# Companion_bot_schematic.net
KiCad netlist of a schematic drawn in EAGLE
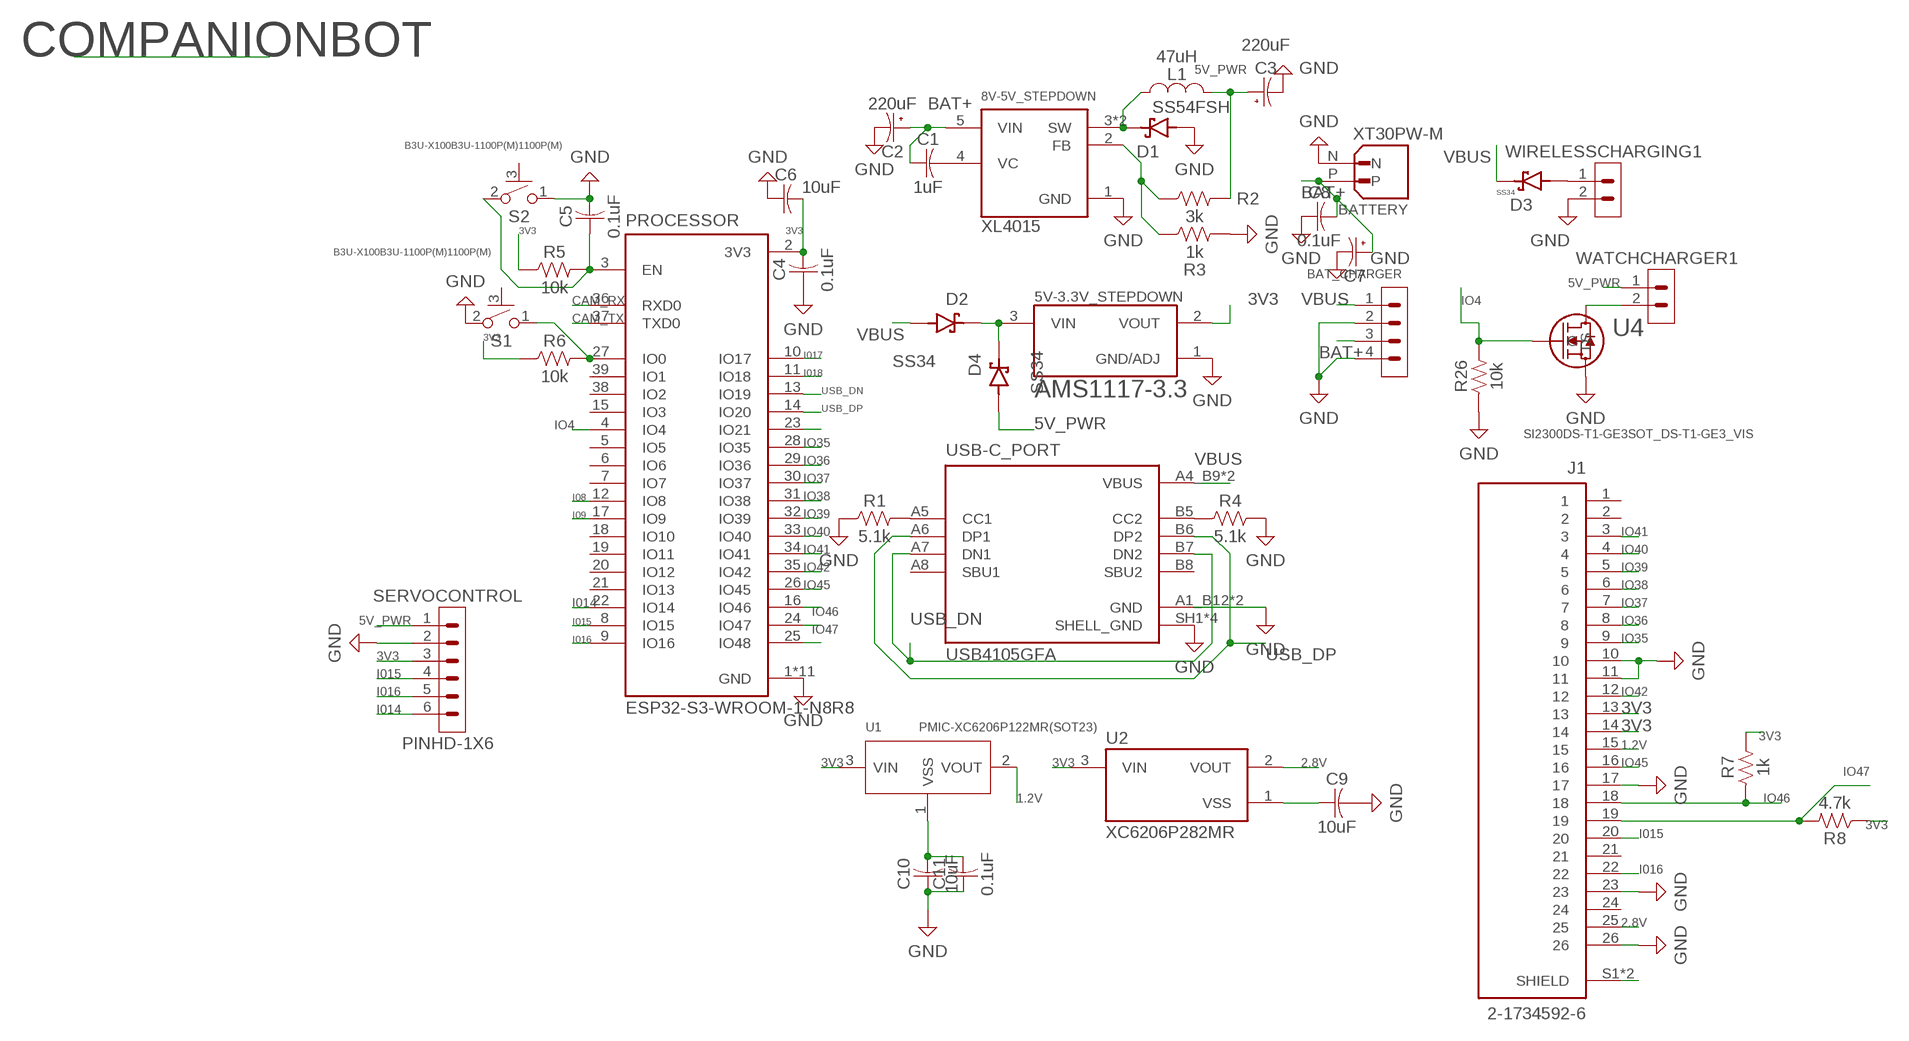
[diagram p0: schematic, sheet 1]

(export (version "E")
  (design (tool "Eeschema 10.0.6"))
  (components
    (comp (ref "5V-3.3V_STEPDOWN")
      (value "AMS1117-3.3")
      (footprint "eagle-import:SOT229P700X180-4N")
      (fields (field (name "MF") "Advanced Monolithic Systems"))
      (libsource (lib "eagle-import") (part "AMS1117-3.3"))
    )
    (comp (ref "8V-5V_STEPDOWN")
      (value "XL4015")
      (footprint "eagle-import:CONV_XL4015")
      (fields (field (name "MF") "XLSEMI"))
      (libsource (lib "eagle-import") (part "XL4015"))
    )
    (comp (ref "BATTERY")
      (value "XT30PW-M")
      (footprint "eagle-import:AMASS_XT30PW-M")
      (fields (field (name "MF") "AMASS"))
      (libsource (lib "eagle-import") (part "XT30PW-M"))
    )
    (comp (ref "BAT_CHARGER")
      (value "PINHD-1X4")
      (footprint "eagle-import:1X04")
      (libsource (lib "eagle-import") (part "PINHD-1X4"))
    )
    (comp (ref "C1")
      (value "1uF")
      (footprint "eagle-import:CAPC1005X60")
      (libsource (lib "eagle-import") (part "C-USCHIP-0402(1005-METRIC)_"))
    )
    (comp (ref "C2")
      (value "220uF")
      (footprint "eagle-import:CAPMP3216X180N")
      (libsource (lib "eagle-import") (part "C-POL-USTANTALUM-1206(3216-METRIC)_"))
    )
    (comp (ref "C3")
      (value "220uF")
      (footprint "eagle-import:CAPMP3216X180N")
      (libsource (lib "eagle-import") (part "C-POL-USTANTALUM-1206(3216-METRIC)_"))
    )
    (comp (ref "C4")
      (value "0.1uF")
      (footprint "eagle-import:CAPC1005X60")
      (libsource (lib "eagle-import") (part "C-USCHIP-0402(1005-METRIC)_"))
    )
    (comp (ref "C5")
      (value "0.1uF")
      (footprint "eagle-import:CAPC1005X60")
      (libsource (lib "eagle-import") (part "C-USCHIP-0402(1005-METRIC)_"))
    )
    (comp (ref "C6")
      (value "10uF")
      (footprint "eagle-import:CAPC1005X60")
      (libsource (lib "eagle-import") (part "C-USCHIP-0402(1005-METRIC)_"))
    )
    (comp (ref "C7")
      (value "C-POL-US_TANTALUM-1206(3216-METRIC)")
      (footprint "eagle-import:CAPMP3216X180N")
      (libsource (lib "eagle-import") (part "C-POL-USTANTALUM-1206(3216-METRIC)_"))
    )
    (comp (ref "C8")
      (value "0.1uF")
      (footprint "eagle-import:CAPC1005X60")
      (libsource (lib "eagle-import") (part "C-USCHIP-0402(1005-METRIC)_"))
    )
    (comp (ref "C9")
      (value "10uF")
      (footprint "eagle-import:CAPC1005X60")
      (libsource (lib "eagle-import") (part "C-USCHIP-0402(1005-METRIC)_"))
    )
    (comp (ref "C10")
      (value "10uF")
      (footprint "eagle-import:CAPC1005X60")
      (libsource (lib "eagle-import") (part "C-USCHIP-0402(1005-METRIC)_"))
    )
    (comp (ref "C11")
      (value "0.1uF")
      (footprint "eagle-import:CAPC1005X60")
      (libsource (lib "eagle-import") (part "C-USCHIP-0402(1005-METRIC)_"))
    )
    (comp (ref "D1")
      (value "SS54FSH")
      (footprint "eagle-import:SODFL4725X110N")
      (fields (field (name "MF") "Taiwan Semiconductor"))
      (libsource (lib "eagle-import") (part "SS54FSH"))
    )
    (comp (ref "D2")
      (value "SS34")
      (footprint "eagle-import:DIO_SS34")
      (fields (field (name "MF") "Taiwan Semiconductor"))
      (libsource (lib "eagle-import") (part "SS34"))
    )
    (comp (ref "D3")
      (value "SS34")
      (footprint "eagle-import:DIO_SS34")
      (fields (field (name "MF") "Taiwan Semiconductor"))
      (libsource (lib "eagle-import") (part "SS34"))
    )
    (comp (ref "D4")
      (value "SS34")
      (footprint "eagle-import:DIO_SS34")
      (fields (field (name "MF") "Taiwan Semiconductor"))
      (libsource (lib "eagle-import") (part "SS34"))
    )
    (comp (ref "J1")
      (value "2-1734592-6")
      (footprint "eagle-import:TE_2-1734592-6")
      (fields (field (name "MF") "TE Connectivity"))
      (libsource (lib "eagle-import") (part "2-1734592-6"))
    )
    (comp (ref "L1")
      (value "47uH")
      (footprint "eagle-import:INDC1006X60N")
      (libsource (lib "eagle-import") (part "LCHIP-0402(1006-METRIC)_"))
    )
    (comp (ref "PROCESSOR")
      (value "ESP32-S3-WROOM-1-N8R8")
      (footprint "eagle-import:XCVR_ESP32S3WROOM1N8R8")
      (fields (field (name "MF") "Espressif Systems"))
      (libsource (lib "eagle-import") (part "ESP32-S3-WROOM-1-N8R8"))
    )
    (comp (ref "R1")
      (value "5.1k")
      (footprint "eagle-import:RESC1005X40")
      (libsource (lib "eagle-import") (part "R-USCHIP-0402(1005-METRIC)_"))
    )
    (comp (ref "R2")
      (value "3k")
      (footprint "eagle-import:RESC1005X40")
      (libsource (lib "eagle-import") (part "R-USCHIP-0402(1005-METRIC)_"))
    )
    (comp (ref "R3")
      (value "1k")
      (footprint "eagle-import:RESC1005X40")
      (libsource (lib "eagle-import") (part "R-USCHIP-0402(1005-METRIC)_"))
    )
    (comp (ref "R4")
      (value "5.1k")
      (footprint "eagle-import:RESC1005X40")
      (libsource (lib "eagle-import") (part "R-USCHIP-0402(1005-METRIC)_"))
    )
    (comp (ref "R5")
      (value "10k")
      (footprint "eagle-import:RESC1005X40")
      (libsource (lib "eagle-import") (part "R-USCHIP-0402(1005-METRIC)_"))
    )
    (comp (ref "R6")
      (value "10k")
      (footprint "eagle-import:RESC1005X40")
      (libsource (lib "eagle-import") (part "R-USCHIP-0402(1005-METRIC)_"))
    )
    (comp (ref "R7")
      (value "1k")
      (footprint "eagle-import:RESC1005X40")
      (libsource (lib "eagle-import") (part "R-USCHIP-0402(1005-METRIC)_"))
    )
    (comp (ref "R8")
      (value "4.7k")
      (footprint "eagle-import:RESC1005X40")
      (libsource (lib "eagle-import") (part "R-USCHIP-0402(1005-METRIC)_"))
    )
    (comp (ref "R26")
      (value "10k")
      (footprint "eagle-import:RESC1005X40")
      (libsource (lib "eagle-import") (part "R-USCHIP-0402(1005-METRIC)_"))
    )
    (comp (ref "S1")
      (value "B3U-X100B3U-1100P(M)1100P(M)")
      (footprint "eagle-import:B3U-1100P(M)")
      (fields (field (name "MANUFACTURER") "Omron Electronics Inc-EMC Div") (field (name "MPN") "B3U-1100PM"))
      (libsource (lib "eagle-import") (part "B3U-X1001100P(M)B3U-1100P(M)"))
    )
    (comp (ref "S2")
      (value "B3U-X100B3U-1100P(M)1100P(M)")
      (footprint "eagle-import:B3U-1100P(M)")
      (fields (field (name "MANUFACTURER") "Omron Electronics Inc-EMC Div") (field (name "MPN") "B3U-1100PM"))
      (libsource (lib "eagle-import") (part "B3U-X1001100P(M)B3U-1100P(M)"))
    )
    (comp (ref "SERVOCONTROL")
      (value "PINHD-1X6")
      (footprint "eagle-import:1X06")
      (libsource (lib "eagle-import") (part "PINHD-1X6"))
    )
    (comp (ref "U1")
      (value "PMIC-XC6206P122MR(SOT23)")
      (footprint "eagle-import:SOT-23")
      (fields (field (name "MF") "Torex") (field (name "MP") "XC6206P122MR"))
      (libsource (lib "eagle-import") (part "PMIC-XC6206P122MR(SOT23)"))
    )
    (comp (ref "U2")
      (value "XC6206P282MR")
      (footprint "eagle-import:VREG_XC6206P282MR")
      (fields (field (name "MF") "Torex Semiconductor Ltd"))
      (libsource (lib "eagle-import") (part "XC6206P282MR"))
    )
    (comp (ref "U4")
      (value "SI2300DS-T1-GE3SOT_DS-T1-GE3_VIS")
      (footprint "eagle-import:SOT_DS-T1-GE3_VIS")
      (fields
        (field (name "MANUFACTURER_PART_NUMBER") "SI2300DS-T1-GE3")
        (field (name "COPYRIGHT") "Copyright (C) 2026 Ultra Librarian. All rights reserved.")
      )
      (libsource (lib "eagle-import") (part "SI2300DS-T1-GE3SOT_DS-T1-GE3_VIS"))
    )
    (comp (ref "USB-C_PORT")
      (value "USB4105GFA")
      (footprint "eagle-import:GCT_USB4105GFA")
      (fields (field (name "MF") "Global Connector Technology"))
      (libsource (lib "eagle-import") (part "USB4105GFA"))
    )
    (comp (ref "WATCHCHARGER1")
      (value "PINHD-1X2")
      (footprint "eagle-import:1X02")
      (libsource (lib "eagle-import") (part "PINHD-1X2"))
    )
    (comp (ref "WIRELESSCHARGING1")
      (value "PINHD-1X2")
      (footprint "eagle-import:1X02")
      (libsource (lib "eagle-import") (part "PINHD-1X2"))
    )
  )
  (nets
    (net (code "1") (name "/1.2V") (class "Default")
      (node (ref "J1") (pin "15") (pinfunction "15_15") (pintype "passive"))
      (node (ref "U1") (pin "2") (pinfunction "VOUT_2") (pintype "output"))
    )
    (net (code "2") (name "/2.8V") (class "Default")
      (node (ref "J1") (pin "25") (pinfunction "25_25") (pintype "passive"))
      (node (ref "U2") (pin "2") (pinfunction "VOUT_2") (pintype "output"))
    )
    (net (code "3") (name "/3V3") (class "Default")
      (node (ref "5V-3.3V_STEPDOWN") (pin "2") (pinfunction "VOUT_2") (pintype "output"))
      (node (ref "C4") (pin "2") (pinfunction "2_2") (pintype "passive"))
      (node (ref "C6") (pin "2") (pinfunction "2_2") (pintype "passive"))
      (node (ref "J1") (pin "13") (pinfunction "13_13") (pintype "passive"))
      (node (ref "J1") (pin "14") (pinfunction "14_14") (pintype "passive"))
      (node (ref "PROCESSOR") (pin "2") (pinfunction "3V3_2") (pintype "power_in"))
      (node (ref "R5") (pin "1") (pinfunction "1_1") (pintype "passive"))
      (node (ref "R6") (pin "1") (pinfunction "1_1") (pintype "passive"))
      (node (ref "R7") (pin "2") (pinfunction "2_2") (pintype "passive"))
      (node (ref "R8") (pin "1") (pinfunction "1_1") (pintype "passive"))
      (node (ref "SERVOCONTROL") (pin "3") (pinfunction "3_3") (pintype "passive"))
      (node (ref "U1") (pin "3") (pinfunction "VIN_3") (pintype "input"))
      (node (ref "U2") (pin "3") (pinfunction "VIN_3") (pintype "input"))
    )
    (net (code "4") (name "/5V_PWR") (class "Default")
      (node (ref "C3") (pin "1") (pinfunction "+_1") (pintype "passive"))
      (node (ref "D4") (pin "A") (pinfunction "A_A") (pintype "passive"))
      (node (ref "L1") (pin "2") (pinfunction "2_2") (pintype "passive"))
      (node (ref "R2") (pin "2") (pinfunction "2_2") (pintype "passive"))
      (node (ref "SERVOCONTROL") (pin "1") (pinfunction "1_1") (pintype "passive"))
      (node (ref "WATCHCHARGER1") (pin "1") (pinfunction "1_1") (pintype "passive"))
    )
    (net (code "5") (name "/BAT+") (class "Default")
      (node (ref "8V-5V_STEPDOWN") (pin "5") (pinfunction "VIN_5") (pintype "input"))
      (node (ref "BATTERY") (pin "P") (pinfunction "P_P") (pintype "power_in"))
      (node (ref "BAT_CHARGER") (pin "3") (pinfunction "3_3") (pintype "passive"))
      (node (ref "C1") (pin "1") (pinfunction "1_1") (pintype "passive"))
      (node (ref "C2") (pin "1") (pinfunction "+_1") (pintype "passive"))
      (node (ref "C7") (pin "1") (pinfunction "+_1") (pintype "passive"))
      (node (ref "C8") (pin "2") (pinfunction "2_2") (pintype "passive"))
    )
    (net (code "6") (name "/CAM_RX") (class "Default")
      (node (ref "PROCESSOR") (pin "36") (pinfunction "RXD0_36") (pintype "bidirectional"))
    )
    (net (code "7") (name "/CAM_TX") (class "Default")
      (node (ref "PROCESSOR") (pin "37") (pinfunction "TXD0_37") (pintype "bidirectional"))
    )
    (net (code "9") (name "/I08") (class "Default")
      (node (ref "PROCESSOR") (pin "12") (pinfunction "IO8_12") (pintype "bidirectional"))
    )
    (net (code "10") (name "/I09") (class "Default")
      (node (ref "PROCESSOR") (pin "17") (pinfunction "IO9_17") (pintype "bidirectional"))
    )
    (net (code "11") (name "/I014") (class "Default")
      (node (ref "PROCESSOR") (pin "22") (pinfunction "IO14_22") (pintype "bidirectional"))
      (node (ref "SERVOCONTROL") (pin "6") (pinfunction "6_6") (pintype "passive"))
    )
    (net (code "12") (name "/I015") (class "Default")
      (node (ref "J1") (pin "20") (pinfunction "20_20") (pintype "passive"))
      (node (ref "PROCESSOR") (pin "8") (pinfunction "IO15_8") (pintype "bidirectional"))
      (node (ref "SERVOCONTROL") (pin "4") (pinfunction "4_4") (pintype "passive"))
    )
    (net (code "13") (name "/I016") (class "Default")
      (node (ref "J1") (pin "22") (pinfunction "22_22") (pintype "passive"))
      (node (ref "PROCESSOR") (pin "9") (pinfunction "IO16_9") (pintype "bidirectional"))
      (node (ref "SERVOCONTROL") (pin "5") (pinfunction "5_5") (pintype "passive"))
    )
    (net (code "14") (name "/I017") (class "Default")
      (node (ref "PROCESSOR") (pin "10") (pinfunction "IO17_10") (pintype "bidirectional"))
    )
    (net (code "15") (name "/I018") (class "Default")
      (node (ref "PROCESSOR") (pin "11") (pinfunction "IO18_11") (pintype "bidirectional"))
    )
    (net (code "16") (name "/IO4") (class "Default")
      (node (ref "PROCESSOR") (pin "4") (pinfunction "IO4_4") (pintype "bidirectional"))
      (node (ref "R26") (pin "2") (pinfunction "2_2") (pintype "passive"))
      (node (ref "U4") (pin "1") (pinfunction "G_1") (pintype "passive"))
    )
    (net (code "17") (name "/IO35") (class "Default")
      (node (ref "J1") (pin "9") (pinfunction "9_9") (pintype "passive"))
      (node (ref "PROCESSOR") (pin "28") (pinfunction "IO35_28") (pintype "bidirectional"))
    )
    (net (code "18") (name "/IO36") (class "Default")
      (node (ref "J1") (pin "8") (pinfunction "8_8") (pintype "passive"))
      (node (ref "PROCESSOR") (pin "29") (pinfunction "IO36_29") (pintype "bidirectional"))
    )
    (net (code "19") (name "/IO37") (class "Default")
      (node (ref "J1") (pin "7") (pinfunction "7_7") (pintype "passive"))
      (node (ref "PROCESSOR") (pin "30") (pinfunction "IO37_30") (pintype "bidirectional"))
    )
    (net (code "20") (name "/IO38") (class "Default")
      (node (ref "J1") (pin "6") (pinfunction "6_6") (pintype "passive"))
      (node (ref "PROCESSOR") (pin "31") (pinfunction "IO38_31") (pintype "bidirectional"))
    )
    (net (code "21") (name "/IO39") (class "Default")
      (node (ref "J1") (pin "5") (pinfunction "5_5") (pintype "passive"))
      (node (ref "PROCESSOR") (pin "32") (pinfunction "IO39_32") (pintype "bidirectional"))
    )
    (net (code "22") (name "/IO40") (class "Default")
      (node (ref "J1") (pin "4") (pinfunction "4_4") (pintype "passive"))
      (node (ref "PROCESSOR") (pin "33") (pinfunction "IO40_33") (pintype "bidirectional"))
    )
    (net (code "23") (name "/IO41") (class "Default")
      (node (ref "J1") (pin "3") (pinfunction "3_3") (pintype "passive"))
      (node (ref "PROCESSOR") (pin "34") (pinfunction "IO41_34") (pintype "bidirectional"))
    )
    (net (code "24") (name "/IO42") (class "Default")
      (node (ref "J1") (pin "12") (pinfunction "12_12") (pintype "passive"))
      (node (ref "PROCESSOR") (pin "35") (pinfunction "IO42_35") (pintype "bidirectional"))
    )
    (net (code "25") (name "/IO45") (class "Default")
      (node (ref "J1") (pin "16") (pinfunction "16_16") (pintype "passive"))
      (node (ref "PROCESSOR") (pin "26") (pinfunction "IO45_26") (pintype "bidirectional"))
    )
    (net (code "26") (name "/IO46") (class "Default")
      (node (ref "J1") (pin "18") (pinfunction "18_18") (pintype "passive"))
      (node (ref "PROCESSOR") (pin "16") (pinfunction "IO46_16") (pintype "bidirectional"))
      (node (ref "R7") (pin "1") (pinfunction "1_1") (pintype "passive"))
    )
    (net (code "27") (name "/IO47") (class "Default")
      (node (ref "J1") (pin "19") (pinfunction "19_19") (pintype "passive"))
      (node (ref "PROCESSOR") (pin "24") (pinfunction "IO47_24") (pintype "bidirectional"))
      (node (ref "R8") (pin "2") (pinfunction "2_2") (pintype "passive"))
    )
    (net (code "28") (name "/USB_DN") (class "Default")
      (node (ref "PROCESSOR") (pin "13") (pinfunction "IO19_13") (pintype "bidirectional"))
      (node (ref "USB-C_PORT") (pin "A7") (pinfunction "DN1_A7") (pintype "bidirectional"))
      (node (ref "USB-C_PORT") (pin "B7") (pinfunction "DN2_B7") (pintype "bidirectional"))
    )
    (net (code "29") (name "/USB_DP") (class "Default")
      (node (ref "PROCESSOR") (pin "14") (pinfunction "IO20_14") (pintype "bidirectional"))
      (node (ref "USB-C_PORT") (pin "A6") (pinfunction "DP1_A6") (pintype "bidirectional"))
      (node (ref "USB-C_PORT") (pin "B6") (pinfunction "DP2_B6") (pintype "bidirectional"))
    )
    (net (code "30") (name "/VBUS") (class "Default")
      (node (ref "BAT_CHARGER") (pin "1") (pinfunction "1_1") (pintype "passive"))
      (node (ref "D2") (pin "A") (pinfunction "A_A") (pintype "passive"))
      (node (ref "D3") (pin "C") (pinfunction "K_C") (pintype "passive"))
      (node (ref "USB-C_PORT") (pin "A4_B9") (pinfunction "VBUS_A4_B9") (pintype "power_in"))
      (node (ref "USB-C_PORT") (pin "B4_A9") (pinfunction "VBUS_B4_A9") (pintype "power_in"))
    )
    (net (code "31") (name "GND") (class "Default")
      (node (ref "5V-3.3V_STEPDOWN") (pin "1") (pinfunction "GND/ADJ_1") (pintype "power_in"))
      (node (ref "8V-5V_STEPDOWN") (pin "1") (pinfunction "GND_1") (pintype "power_in"))
      (node (ref "BATTERY") (pin "N") (pinfunction "N_N") (pintype "power_in"))
      (node (ref "BAT_CHARGER") (pin "2") (pinfunction "2_2") (pintype "passive"))
      (node (ref "BAT_CHARGER") (pin "4") (pinfunction "4_4") (pintype "passive"))
      (node (ref "C10") (pin "1") (pinfunction "1_1") (pintype "passive"))
      (node (ref "C11") (pin "1") (pinfunction "1_1") (pintype "passive"))
      (node (ref "C2") (pin "2") (pinfunction "-_2") (pintype "passive"))
      (node (ref "C3") (pin "2") (pinfunction "-_2") (pintype "passive"))
      (node (ref "C4") (pin "1") (pinfunction "1_1") (pintype "passive"))
      (node (ref "C5") (pin "2") (pinfunction "2_2") (pintype "passive"))
      (node (ref "C6") (pin "1") (pinfunction "1_1") (pintype "passive"))
      (node (ref "C7") (pin "2") (pinfunction "-_2") (pintype "passive"))
      (node (ref "C8") (pin "1") (pinfunction "1_1") (pintype "passive"))
      (node (ref "C9") (pin "2") (pinfunction "2_2") (pintype "passive"))
      (node (ref "D1") (pin "A") (pinfunction "A_A") (pintype "passive"))
      (node (ref "J1") (pin "10") (pinfunction "10_10") (pintype "passive"))
      (node (ref "J1") (pin "11") (pinfunction "11_11") (pintype "passive"))
      (node (ref "J1") (pin "17") (pinfunction "17_17") (pintype "passive"))
      (node (ref "J1") (pin "23") (pinfunction "23_23") (pintype "passive"))
      (node (ref "J1") (pin "26") (pinfunction "26_26") (pintype "passive"))
      (node (ref "PROCESSOR") (pin "1") (pinfunction "GND_1") (pintype "power_in"))
      (node (ref "PROCESSOR") (pin "40") (pinfunction "GND_40") (pintype "power_in"))
      (node (ref "PROCESSOR") (pin "41_1") (pinfunction "GND_41_1") (pintype "power_in"))
      (node (ref "PROCESSOR") (pin "41_2") (pinfunction "GND_41_2") (pintype "power_in"))
      (node (ref "PROCESSOR") (pin "41_3") (pinfunction "GND_41_3") (pintype "power_in"))
      (node (ref "PROCESSOR") (pin "41_4") (pinfunction "GND_41_4") (pintype "power_in"))
      (node (ref "PROCESSOR") (pin "41_5") (pinfunction "GND_41_5") (pintype "power_in"))
      (node (ref "PROCESSOR") (pin "41_6") (pinfunction "GND_41_6") (pintype "power_in"))
      (node (ref "PROCESSOR") (pin "41_7") (pinfunction "GND_41_7") (pintype "power_in"))
      (node (ref "PROCESSOR") (pin "41_8") (pinfunction "GND_41_8") (pintype "power_in"))
      (node (ref "PROCESSOR") (pin "41_9") (pinfunction "GND_41_9") (pintype "power_in"))
      (node (ref "R1") (pin "1") (pinfunction "1_1") (pintype "passive"))
      (node (ref "R26") (pin "1") (pinfunction "1_1") (pintype "passive"))
      (node (ref "R3") (pin "2") (pinfunction "2_2") (pintype "passive"))
      (node (ref "R4") (pin "2") (pinfunction "2_2") (pintype "passive"))
      (node (ref "S1") (pin "2") (pinfunction "1_2") (pintype "bidirectional"))
      (node (ref "S2") (pin "1") (pinfunction "2_1") (pintype "bidirectional"))
      (node (ref "SERVOCONTROL") (pin "2") (pinfunction "2_2") (pintype "passive"))
      (node (ref "U4") (pin "3") (pinfunction "S_3") (pintype "passive"))
      (node (ref "USB-C_PORT") (pin "A1_B12") (pinfunction "GND_A1_B12") (pintype "power_in"))
      (node (ref "USB-C_PORT") (pin "B1_A12") (pinfunction "GND_B1_A12") (pintype "power_in"))
      (node (ref "USB-C_PORT") (pin "SH1") (pinfunction "SHELL_GND_SH1") (pintype "power_in"))
      (node (ref "USB-C_PORT") (pin "SH2") (pinfunction "SHELL_GND_SH2") (pintype "power_in"))
      (node (ref "USB-C_PORT") (pin "SH3") (pinfunction "SHELL_GND_SH3") (pintype "power_in"))
      (node (ref "USB-C_PORT") (pin "SH4") (pinfunction "SHELL_GND_SH4") (pintype "power_in"))
      (node (ref "WIRELESSCHARGING1") (pin "2") (pinfunction "2_2") (pintype "passive"))
    )
    (net (code "32") (name "Net-(5V-3.3V_STEPDOWN-VIN)") (class "Default")
      (node (ref "5V-3.3V_STEPDOWN") (pin "3") (pinfunction "VIN_3") (pintype "input"))
      (node (ref "D2") (pin "C") (pinfunction "K_C") (pintype "passive"))
      (node (ref "D4") (pin "C") (pinfunction "K_C") (pintype "passive"))
    )
    (net (code "33") (name "Net-(8V-5V_STEPDOWN-FB)") (class "Default")
      (node (ref "8V-5V_STEPDOWN") (pin "2") (pinfunction "FB_2") (pintype "input"))
      (node (ref "R2") (pin "1") (pinfunction "1_1") (pintype "passive"))
      (node (ref "R3") (pin "1") (pinfunction "1_1") (pintype "passive"))
    )
    (net (code "34") (name "Net-(8V-5V_STEPDOWN-VC)") (class "Default")
      (node (ref "8V-5V_STEPDOWN") (pin "4") (pinfunction "VC_4") (pintype "passive"))
      (node (ref "C1") (pin "2") (pinfunction "2_2") (pintype "passive"))
    )
    (net (code "35") (name "Net-(D1-K)") (class "Default")
      (node (ref "8V-5V_STEPDOWN") (pin "3") (pinfunction "SW_3") (pintype "output"))
      (node (ref "8V-5V_STEPDOWN") (pin "3.1") (pinfunction "SW_3.1") (pintype "output"))
      (node (ref "D1") (pin "C") (pinfunction "K_C") (pintype "passive"))
      (node (ref "L1") (pin "1") (pinfunction "1_1") (pintype "passive"))
    )
    (net (code "36") (name "Net-(D3-PadA)") (class "Default")
      (node (ref "D3") (pin "A") (pinfunction "A_A") (pintype "passive"))
      (node (ref "WIRELESSCHARGING1") (pin "1") (pinfunction "1_1") (pintype "passive"))
    )
    (net (code "37") (name "Net-(J1-SHIELD-PadS1)") (class "Default")
      (node (ref "J1") (pin "S1") (pinfunction "SHIELD_S1") (pintype "passive"))
      (node (ref "J1") (pin "S2") (pinfunction "SHIELD_S2") (pintype "passive"))
    )
    (net (code "38") (name "Net-(PROCESSOR-EN)") (class "Default")
      (node (ref "C5") (pin "1") (pinfunction "1_1") (pintype "passive"))
      (node (ref "PROCESSOR") (pin "3") (pinfunction "EN_3") (pintype "input"))
      (node (ref "R5") (pin "2") (pinfunction "2_2") (pintype "passive"))
      (node (ref "S2") (pin "2") (pinfunction "1_2") (pintype "bidirectional"))
    )
    (net (code "39") (name "Net-(PROCESSOR-IO0)") (class "Default")
      (node (ref "PROCESSOR") (pin "27") (pinfunction "IO0_27") (pintype "bidirectional"))
      (node (ref "R6") (pin "2") (pinfunction "2_2") (pintype "passive"))
      (node (ref "S1") (pin "1") (pinfunction "2_1") (pintype "bidirectional"))
    )
    (net (code "40") (name "Net-(U1-VSS)") (class "Default")
      (node (ref "C10") (pin "2") (pinfunction "2_2") (pintype "passive"))
      (node (ref "C11") (pin "2") (pinfunction "2_2") (pintype "passive"))
      (node (ref "U1") (pin "1") (pinfunction "VSS_1") (pintype "power_in"))
    )
    (net (code "41") (name "Net-(U2-VSS)") (class "Default")
      (node (ref "C9") (pin "1") (pinfunction "1_1") (pintype "passive"))
      (node (ref "U2") (pin "1") (pinfunction "VSS_1") (pintype "power_in"))
    )
    (net (code "42") (name "Net-(U4-D)") (class "Default")
      (node (ref "U4") (pin "2") (pinfunction "D_2") (pintype "passive"))
      (node (ref "WATCHCHARGER1") (pin "2") (pinfunction "2_2") (pintype "passive"))
    )
    (net (code "43") (name "Net-(USB-C_PORT-CC1)") (class "Default")
      (node (ref "R1") (pin "2") (pinfunction "2_2") (pintype "passive"))
      (node (ref "USB-C_PORT") (pin "A5") (pinfunction "CC1_A5") (pintype "bidirectional"))
    )
    (net (code "44") (name "Net-(USB-C_PORT-CC2)") (class "Default")
      (node (ref "R4") (pin "1") (pinfunction "1_1") (pintype "passive"))
      (node (ref "USB-C_PORT") (pin "B5") (pinfunction "CC2_B5") (pintype "bidirectional"))
    )
    (net (code "45") (name "unconnected-(J1-Pad1)") (class "Default")
      (node (ref "J1") (pin "1") (pinfunction "1_1") (pintype "passive"))
    )
    (net (code "46") (name "unconnected-(J1-Pad2)") (class "Default")
      (node (ref "J1") (pin "2") (pinfunction "2_2") (pintype "passive"))
    )
    (net (code "47") (name "unconnected-(J1-Pad21)") (class "Default")
      (node (ref "J1") (pin "21") (pinfunction "21_21") (pintype "passive"))
    )
    (net (code "48") (name "unconnected-(J1-Pad24)") (class "Default")
      (node (ref "J1") (pin "24") (pinfunction "24_24") (pintype "passive"))
    )
    (net (code "49") (name "unconnected-(PROCESSOR-IO1-Pad39)") (class "Default")
      (node (ref "PROCESSOR") (pin "39") (pinfunction "IO1_39") (pintype "bidirectional"))
    )
    (net (code "50") (name "unconnected-(PROCESSOR-IO2-Pad38)") (class "Default")
      (node (ref "PROCESSOR") (pin "38") (pinfunction "IO2_38") (pintype "bidirectional"))
    )
    (net (code "51") (name "unconnected-(PROCESSOR-IO3-Pad15)") (class "Default")
      (node (ref "PROCESSOR") (pin "15") (pinfunction "IO3_15") (pintype "bidirectional"))
    )
    (net (code "52") (name "unconnected-(PROCESSOR-IO5-Pad5)") (class "Default")
      (node (ref "PROCESSOR") (pin "5") (pinfunction "IO5_5") (pintype "bidirectional"))
    )
    (net (code "53") (name "unconnected-(PROCESSOR-IO6-Pad6)") (class "Default")
      (node (ref "PROCESSOR") (pin "6") (pinfunction "IO6_6") (pintype "bidirectional"))
    )
    (net (code "54") (name "unconnected-(PROCESSOR-IO7-Pad7)") (class "Default")
      (node (ref "PROCESSOR") (pin "7") (pinfunction "IO7_7") (pintype "bidirectional"))
    )
    (net (code "55") (name "unconnected-(PROCESSOR-IO10-Pad18)") (class "Default")
      (node (ref "PROCESSOR") (pin "18") (pinfunction "IO10_18") (pintype "bidirectional"))
    )
    (net (code "56") (name "unconnected-(PROCESSOR-IO11-Pad19)") (class "Default")
      (node (ref "PROCESSOR") (pin "19") (pinfunction "IO11_19") (pintype "bidirectional"))
    )
    (net (code "57") (name "unconnected-(PROCESSOR-IO12-Pad20)") (class "Default")
      (node (ref "PROCESSOR") (pin "20") (pinfunction "IO12_20") (pintype "bidirectional"))
    )
    (net (code "58") (name "unconnected-(PROCESSOR-IO13-Pad21)") (class "Default")
      (node (ref "PROCESSOR") (pin "21") (pinfunction "IO13_21") (pintype "bidirectional"))
    )
    (net (code "59") (name "unconnected-(PROCESSOR-IO21-Pad23)") (class "Default")
      (node (ref "PROCESSOR") (pin "23") (pinfunction "IO21_23") (pintype "bidirectional"))
    )
    (net (code "60") (name "unconnected-(PROCESSOR-IO48-Pad25)") (class "Default")
      (node (ref "PROCESSOR") (pin "25") (pinfunction "IO48_25") (pintype "bidirectional"))
    )
    (net (code "61") (name "unconnected-(S1-Pad3)") (class "Default")
      (node (ref "S1") (pin "3") (pinfunction "3_3") (pintype "bidirectional"))
    )
    (net (code "62") (name "unconnected-(S2-Pad3)") (class "Default")
      (node (ref "S2") (pin "3") (pinfunction "3_3") (pintype "bidirectional"))
    )
    (net (code "63") (name "unconnected-(USB-C_PORT-SBU1-PadA8)") (class "Default")
      (node (ref "USB-C_PORT") (pin "A8") (pinfunction "SBU1_A8") (pintype "bidirectional"))
    )
    (net (code "64") (name "unconnected-(USB-C_PORT-SBU2-PadB8)") (class "Default")
      (node (ref "USB-C_PORT") (pin "B8") (pinfunction "SBU2_B8") (pintype "bidirectional"))
    )
  )
)
